# LilyPad_Temperature_Sensor.net
KiCad netlist of a schematic drawn in EAGLE
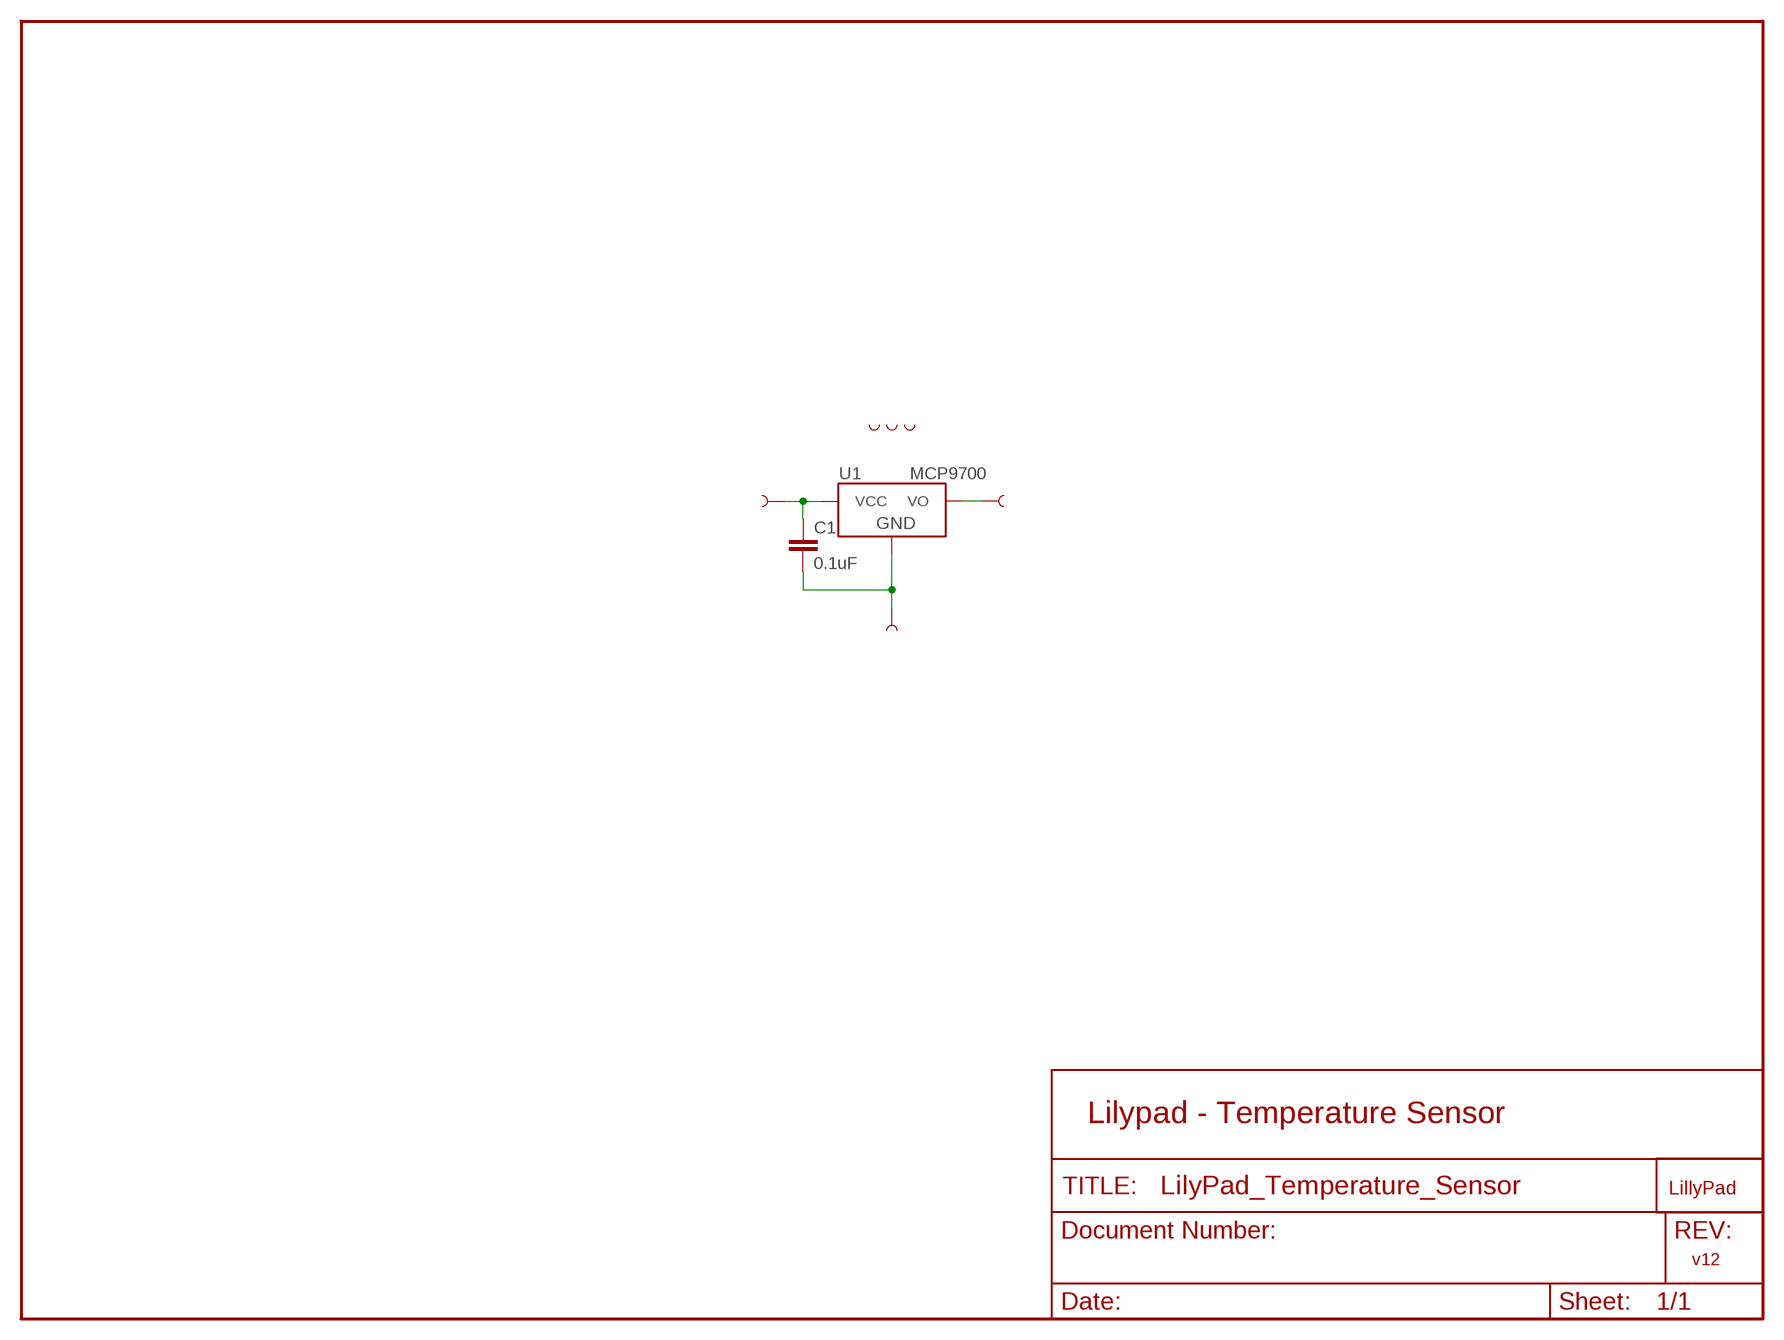
[diagram p0: schematic, sheet 1]

(export (version "E")
  (design (tool "Eeschema 10.0.6"))
  (components
    (comp (ref "C1")
      (value "0.1uF")
      (footprint "eagle-import:0603-CAP")
      (libsource (lib "eagle-import") (part "CAP0603-CAP"))
    )
    (comp (ref "TEMP+")
      (value "SEWTAP6")
      (footprint "eagle-import:PETAL-SMALL-2SIDE")
      (libsource (lib "eagle-import") (part "SEWTAP6"))
    )
    (comp (ref "TEMP-")
      (value "SEWTAP6")
      (footprint "eagle-import:PETAL-SMALL-2SIDE")
      (libsource (lib "eagle-import") (part "SEWTAP6"))
    )
    (comp (ref "TEMP1")
      (value "SEWTAP-NOHOLE2")
      (footprint "eagle-import:PETAL-NOHOLE-2SIDE")
      (libsource (lib "eagle-import") (part "SEWTAP-NOHOLE2"))
    )
    (comp (ref "TEMP2")
      (value "SEWTAP-NOHOLE2")
      (footprint "eagle-import:PETAL-NOHOLE-2SIDE")
      (libsource (lib "eagle-import") (part "SEWTAP-NOHOLE2"))
    )
    (comp (ref "TEMP3")
      (value "SEWTAP-NOHOLE2")
      (footprint "eagle-import:PETAL-NOHOLE-2SIDE")
      (libsource (lib "eagle-import") (part "SEWTAP-NOHOLE2"))
    )
    (comp (ref "TEMPS")
      (value "SEWTAP6")
      (footprint "eagle-import:PETAL-SMALL-2SIDE")
      (libsource (lib "eagle-import") (part "SEWTAP6"))
    )
    (comp (ref "U$2")
      (value "LOGO-LPLP")
      (footprint "eagle-import:LOGO-LILYPAD")
      (libsource (lib "eagle-import") (part "LOGO-LPLP"))
    )
    (comp (ref "U1")
      (value "MCP9700")
      (footprint "eagle-import:SOT23-3")
      (libsource (lib "eagle-import") (part "MCP9700SMD"))
    )
  )
  (nets
    (net (code "1") (name "Net-(U1-GND)") (class "Default")
      (node (ref "C1") (pin "2") (pinfunction "2_2") (pintype "passive"))
      (node (ref "TEMP-") (pin "1") (pinfunction "1_1") (pintype "bidirectional"))
      (node (ref "U1") (pin "3") (pinfunction "GND_3") (pintype "bidirectional"))
    )
    (net (code "2") (name "Net-(U1-VCC)") (class "Default")
      (node (ref "C1") (pin "1") (pinfunction "1_1") (pintype "passive"))
      (node (ref "TEMP+") (pin "1") (pinfunction "1_1") (pintype "bidirectional"))
      (node (ref "U1") (pin "1") (pinfunction "VCC_1") (pintype "bidirectional"))
    )
    (net (code "3") (name "Net-(U1-VO)") (class "Default")
      (node (ref "TEMPS") (pin "1") (pinfunction "1_1") (pintype "bidirectional"))
      (node (ref "U1") (pin "2") (pinfunction "VO_2") (pintype "bidirectional"))
    )
  )
)
